# iwing-mrf_shield10.net
KiCad netlist of a schematic drawn in EAGLE
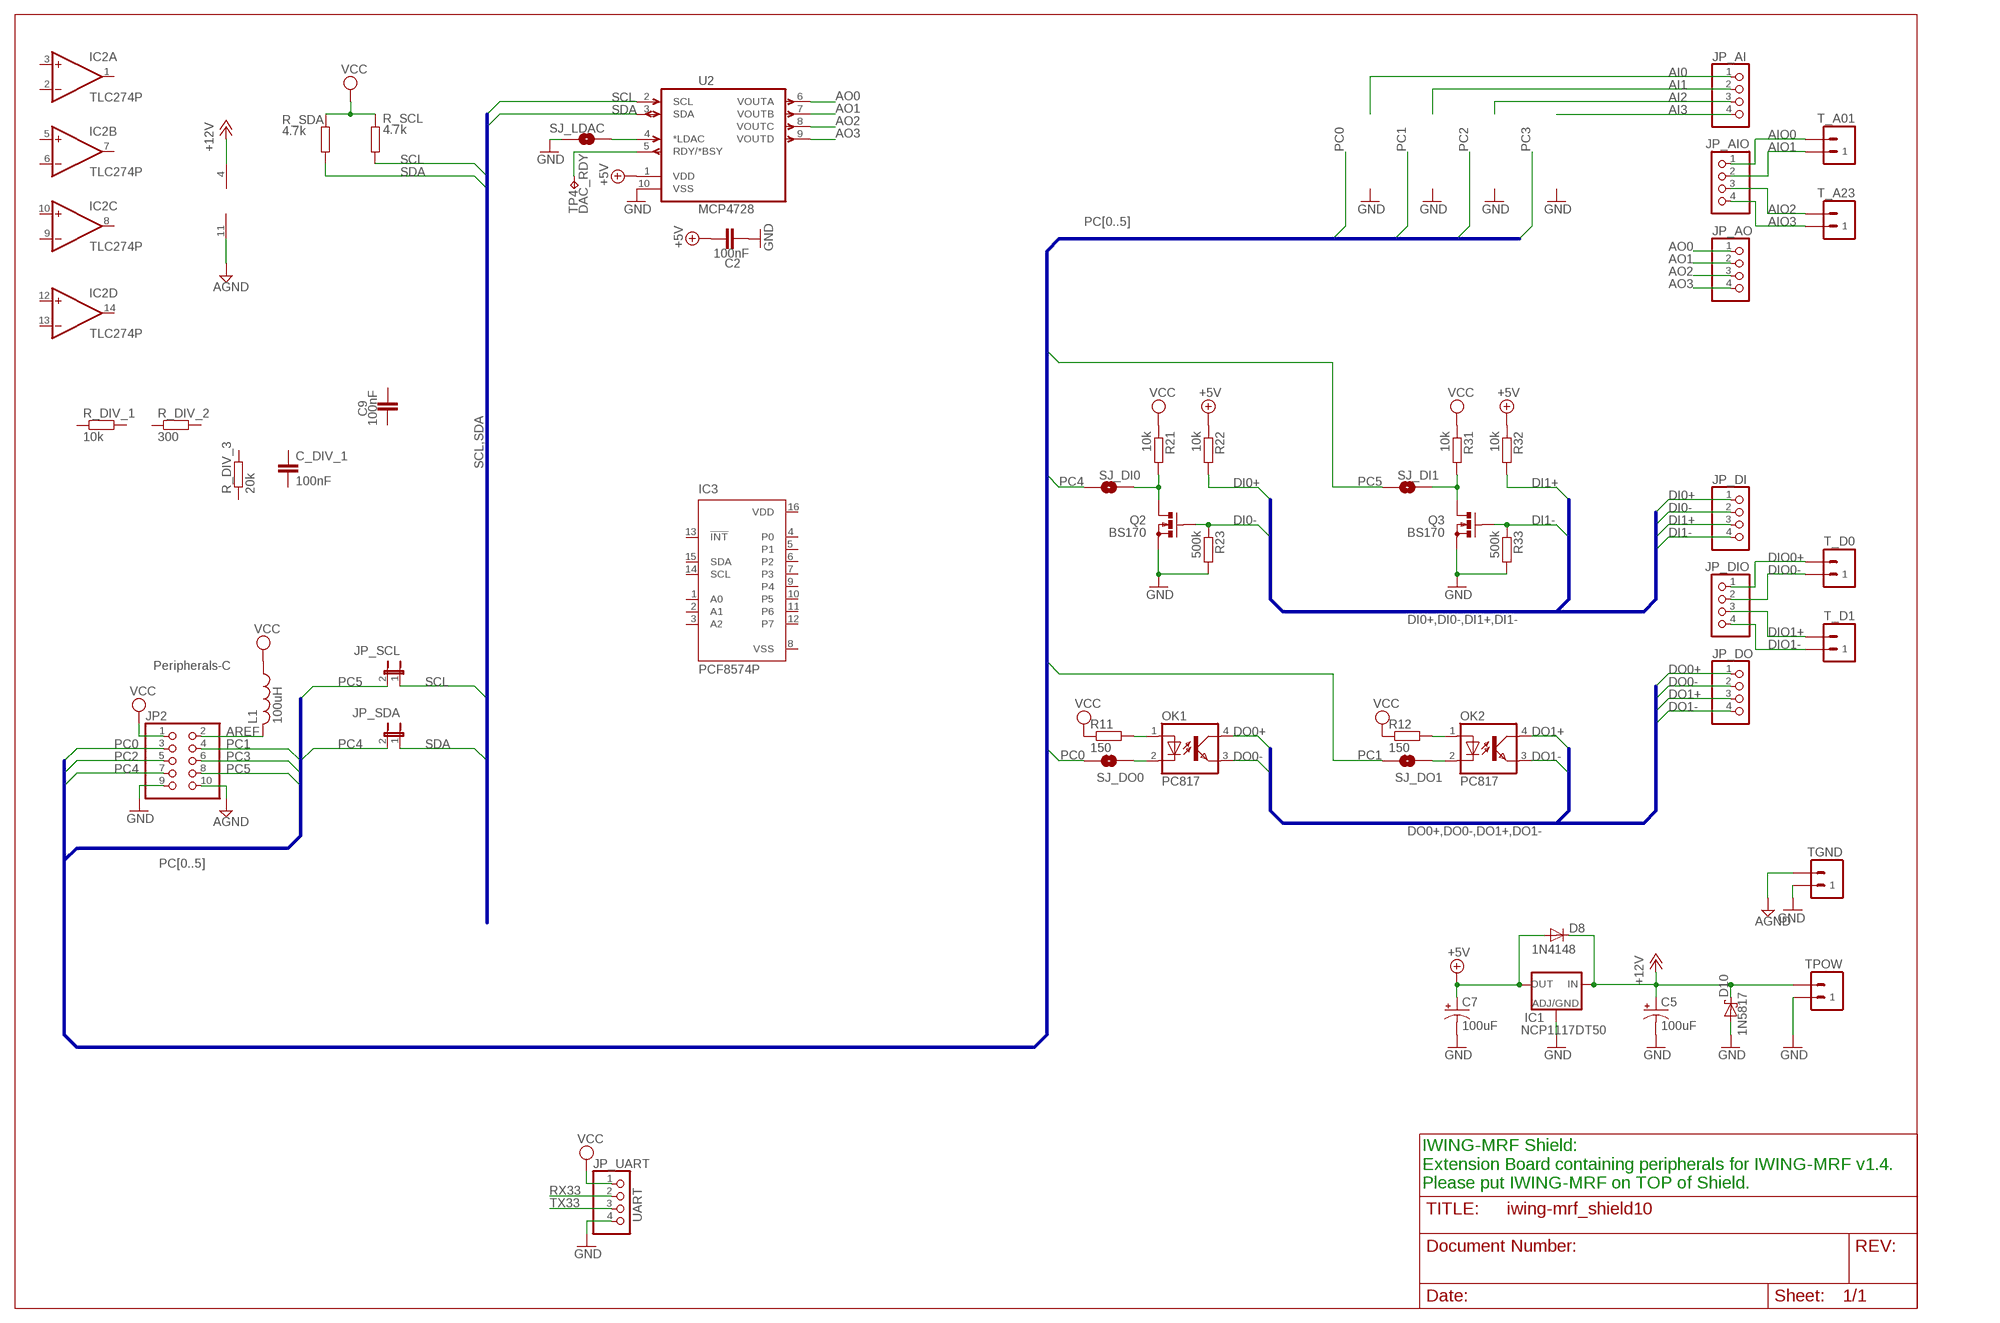
[diagram p0: schematic, sheet 1]

(export (version "E")
  (design (tool "Eeschema 10.0.6"))
  (components
    (comp (ref "C2")
      (value "100nF")
      (footprint "eagle-import:RCL_C050-025X075")
      (libsource (lib "eagle-import") (part "RCL_C-EU050-025X075"))
    )
    (comp (ref "C5")
      (value "100uF")
      (footprint "eagle-import:RCL_E2,5-7")
      (libsource (lib "eagle-import") (part "RCL_CPOL-USE2.5-7"))
    )
    (comp (ref "C7")
      (value "100uF")
      (footprint "eagle-import:RCL_E2,5-7")
      (libsource (lib "eagle-import") (part "RCL_CPOL-USE2.5-7"))
    )
    (comp (ref "C9")
      (value "100nF")
      (footprint "eagle-import:RCL_C050-025X075")
      (libsource (lib "eagle-import") (part "RCL_C-EU050-025X075"))
    )
    (comp (ref "C_DIV_1")
      (value "100nF")
      (footprint "eagle-import:RCL_C050-025X075")
      (libsource (lib "eagle-import") (part "RCL_C-EU050-025X075"))
    )
    (comp (ref "D8")
      (value "1N4148")
      (footprint "eagle-import:DO35-100V")
      (libsource (lib "eagle-import") (part "1N4148-V"))
    )
    (comp (ref "D10")
      (value "1N5817")
      (footprint "eagle-import:DO41-150V")
      (libsource (lib "eagle-import") (part "1N5819-V"))
    )
    (comp (ref "IC1")
      (value "NCP1117DT50")
      (footprint "eagle-import:DPACK")
      (libsource (lib "eagle-import") (part "NCP1117?DT50"))
    )
    (comp (ref "IC2")
      (value "TLC274P")
      (footprint "eagle-import:DIL14")
      (libsource (lib "eagle-import") (part "TLC274P"))
    )
    (comp (ref "IC3")
      (value "PCF8574P")
      (footprint "eagle-import:DIL16")
      (fields (field (name "MPN") "PCF8574PN"))
      (libsource (lib "eagle-import") (part "PCF8574P"))
    )
    (comp (ref "JP2")
      (value "HEADER-2X5")
      (footprint "eagle-import:2X05")
      (libsource (lib "eagle-import") (part "HEADER-2X5"))
    )
    (comp (ref "JP_AI")
      (value "HEADER-1X4ROUND")
      (footprint "eagle-import:1X04_ROUND")
      (libsource (lib "eagle-import") (part "HEADER-1X4ROUND"))
    )
    (comp (ref "JP_AIO")
      (value "HEADER-1X4ROUND")
      (footprint "eagle-import:1X04_ROUND")
      (libsource (lib "eagle-import") (part "HEADER-1X4ROUND"))
    )
    (comp (ref "JP_AO")
      (value "HEADER-1X4ROUND")
      (footprint "eagle-import:1X04_ROUND")
      (libsource (lib "eagle-import") (part "HEADER-1X4ROUND"))
    )
    (comp (ref "JP_DI")
      (value "HEADER-1X4ROUND")
      (footprint "eagle-import:1X04_ROUND")
      (libsource (lib "eagle-import") (part "HEADER-1X4ROUND"))
    )
    (comp (ref "JP_DIO")
      (value "HEADER-1X4ROUND")
      (footprint "eagle-import:1X04_ROUND")
      (libsource (lib "eagle-import") (part "HEADER-1X4ROUND"))
    )
    (comp (ref "JP_DO")
      (value "HEADER-1X4ROUND")
      (footprint "eagle-import:1X04_ROUND")
      (libsource (lib "eagle-import") (part "HEADER-1X4ROUND"))
    )
    (comp (ref "JP_SCL")
      (value "JUMPER-2SMD-NO")
      (footprint "eagle-import:SJ_2S-NO")
      (libsource (lib "eagle-import") (part "JUMPER-2SMD-NO"))
    )
    (comp (ref "JP_SDA")
      (value "JUMPER-2SMD-NO")
      (footprint "eagle-import:SJ_2S-NO")
      (libsource (lib "eagle-import") (part "JUMPER-2SMD-NO"))
    )
    (comp (ref "JP_UART")
      (value "HEADER-1X4ROUND")
      (footprint "eagle-import:1X04_ROUND")
      (libsource (lib "eagle-import") (part "HEADER-1X4ROUND"))
    )
    (comp (ref "L1")
      (value "100uH")
      (footprint "eagle-import:0204_5")
      (libsource (lib "eagle-import") (part "L-US0204/5"))
    )
    (comp (ref "OK1")
      (value "PC817")
      (footprint "eagle-import:DIL04")
      (fields (field (name "MPN") "PC817X4J000F"))
      (libsource (lib "eagle-import") (part "PC817"))
    )
    (comp (ref "OK2")
      (value "PC817")
      (footprint "eagle-import:DIL04")
      (fields (field (name "MPN") "PC817X4J000F"))
      (libsource (lib "eagle-import") (part "PC817"))
    )
    (comp (ref "Q2")
      (value "BS170")
      (footprint "eagle-import:TO92-")
      (libsource (lib "eagle-import") (part "BS170"))
    )
    (comp (ref "Q3")
      (value "BS170")
      (footprint "eagle-import:TO92-")
      (libsource (lib "eagle-import") (part "BS170"))
    )
    (comp (ref "R11")
      (value "150")
      (footprint "eagle-import:0204_5")
      (libsource (lib "eagle-import") (part "R-EU_0204/5"))
    )
    (comp (ref "R12")
      (value "150")
      (footprint "eagle-import:0204_5")
      (libsource (lib "eagle-import") (part "R-EU_0204/5"))
    )
    (comp (ref "R21")
      (value "10k")
      (footprint "eagle-import:0204_5")
      (libsource (lib "eagle-import") (part "R-EU_0204/5"))
    )
    (comp (ref "R22")
      (value "10k")
      (footprint "eagle-import:0204_5")
      (libsource (lib "eagle-import") (part "R-EU_0204/5"))
    )
    (comp (ref "R23")
      (value "500k")
      (footprint "eagle-import:0204_5")
      (libsource (lib "eagle-import") (part "R-EU_0204/5"))
    )
    (comp (ref "R31")
      (value "10k")
      (footprint "eagle-import:0204_5")
      (libsource (lib "eagle-import") (part "R-EU_0204/5"))
    )
    (comp (ref "R32")
      (value "10k")
      (footprint "eagle-import:0204_5")
      (libsource (lib "eagle-import") (part "R-EU_0204/5"))
    )
    (comp (ref "R33")
      (value "500k")
      (footprint "eagle-import:0204_5")
      (libsource (lib "eagle-import") (part "R-EU_0204/5"))
    )
    (comp (ref "R_DIV_1")
      (value "10k")
      (footprint "eagle-import:0204_5")
      (libsource (lib "eagle-import") (part "R-EU_0204/5"))
    )
    (comp (ref "R_DIV_2")
      (value "300")
      (footprint "eagle-import:0204_5")
      (libsource (lib "eagle-import") (part "R-EU_0204/5"))
    )
    (comp (ref "R_DIV_3")
      (value "20k")
      (footprint "eagle-import:0204_5")
      (libsource (lib "eagle-import") (part "R-EU_0204/5"))
    )
    (comp (ref "R_SCL")
      (value "4.7k")
      (footprint "eagle-import:0204_5")
      (libsource (lib "eagle-import") (part "R-EU_0204/5"))
    )
    (comp (ref "R_SDA")
      (value "4.7k")
      (footprint "eagle-import:0204_5")
      (libsource (lib "eagle-import") (part "R-EU_0204/5"))
    )
    (comp (ref "SJ_DI0")
      (value "SOLDERJUMPERNO")
      (footprint "eagle-import:SJ_2S-NO")
      (libsource (lib "eagle-import") (part "SOLDERJUMPERNO"))
    )
    (comp (ref "SJ_DI1")
      (value "SOLDERJUMPERNO")
      (footprint "eagle-import:SJ_2S-NO")
      (libsource (lib "eagle-import") (part "SOLDERJUMPERNO"))
    )
    (comp (ref "SJ_DO0")
      (value "SOLDERJUMPERNO")
      (footprint "eagle-import:SJ_2S-NO")
      (libsource (lib "eagle-import") (part "SOLDERJUMPERNO"))
    )
    (comp (ref "SJ_DO1")
      (value "SOLDERJUMPERNO")
      (footprint "eagle-import:SJ_2S-NO")
      (libsource (lib "eagle-import") (part "SOLDERJUMPERNO"))
    )
    (comp (ref "SJ_LDAC")
      (value "SOLDERJUMPERNO")
      (footprint "eagle-import:SJ_2S-NO")
      (libsource (lib "eagle-import") (part "SOLDERJUMPERNO"))
    )
    (comp (ref "TGND")
      (value "ST02-5MM")
      (footprint "eagle-import:EK500V-02P")
      (libsource (lib "eagle-import") (part "ST02-5MM"))
    )
    (comp (ref "TP4")
      (value "TPPAD1-13")
      (footprint "eagle-import:P1-13")
      (fields (field (name "TP_SIGNAL_NAME") "DAC_RDY"))
      (libsource (lib "eagle-import") (part "TPPAD1-13"))
    )
    (comp (ref "TPOW")
      (value "ST02-5MM")
      (footprint "eagle-import:EK500V-02P")
      (libsource (lib "eagle-import") (part "ST02-5MM"))
    )
    (comp (ref "T_A01")
      (value "ST02-5MM")
      (footprint "eagle-import:EK500V-02P")
      (libsource (lib "eagle-import") (part "ST02-5MM"))
    )
    (comp (ref "T_A23")
      (value "ST02-5MM")
      (footprint "eagle-import:EK500V-02P")
      (libsource (lib "eagle-import") (part "ST02-5MM"))
    )
    (comp (ref "T_D0")
      (value "ST02-5MM")
      (footprint "eagle-import:EK500V-02P")
      (libsource (lib "eagle-import") (part "ST02-5MM"))
    )
    (comp (ref "T_D1")
      (value "ST02-5MM")
      (footprint "eagle-import:EK500V-02P")
      (libsource (lib "eagle-import") (part "ST02-5MM"))
    )
    (comp (ref "U2")
      (value "MCP4728")
      (footprint "eagle-import:MSOP-10")
      (libsource (lib "eagle-import") (part "MCP4728-E/UN"))
    )
  )
  (nets
    (net (code "1") (name "+5V") (class "Default")
      (node (ref "C2") (pin "1") (pinfunction "1_1") (pintype "passive"))
      (node (ref "C7") (pin "+") (pinfunction "+_+") (pintype "passive"))
      (node (ref "D8") (pin "A") (pinfunction "A_A") (pintype "passive"))
      (node (ref "IC1") (pin "4") (pinfunction "OUT_4") (pintype "passive"))
      (node (ref "R22") (pin "1") (pinfunction "1_1") (pintype "passive"))
      (node (ref "R32") (pin "1") (pinfunction "1_1") (pintype "passive"))
      (node (ref "U2") (pin "1") (pinfunction "VDD_1") (pintype "power_in"))
    )
    (net (code "2") (name "+12V") (class "Default")
      (node (ref "C5") (pin "+") (pinfunction "+_+") (pintype "passive"))
      (node (ref "D10") (pin "C") (pinfunction "C_C") (pintype "passive"))
      (node (ref "D8") (pin "C") (pinfunction "C_C") (pintype "passive"))
      (node (ref "IC1") (pin "3") (pinfunction "IN_3") (pintype "input"))
      (node (ref "IC2") (pin "4") (pinfunction "V+_4") (pintype "power_in"))
      (node (ref "TPOW") (pin "P$2") (pinfunction "2_P$2") (pintype "passive"))
    )
    (net (code "3") (name "/AI0") (class "Default")
      (node (ref "JP_AI") (pin "1") (pinfunction "1_1") (pintype "passive"))
    )
    (net (code "4") (name "/AI1") (class "Default")
      (node (ref "JP_AI") (pin "2") (pinfunction "2_2") (pintype "passive"))
    )
    (net (code "5") (name "/AI2") (class "Default")
      (node (ref "JP_AI") (pin "3") (pinfunction "3_3") (pintype "passive"))
    )
    (net (code "6") (name "/AI3") (class "Default")
      (node (ref "JP_AI") (pin "4") (pinfunction "4_4") (pintype "passive"))
    )
    (net (code "7") (name "/AIO0") (class "Default")
      (node (ref "JP_AIO") (pin "1") (pinfunction "1_1") (pintype "passive"))
      (node (ref "T_A01") (pin "P$2") (pinfunction "2_P$2") (pintype "passive"))
    )
    (net (code "8") (name "/AIO1") (class "Default")
      (node (ref "JP_AIO") (pin "2") (pinfunction "2_2") (pintype "passive"))
      (node (ref "T_A01") (pin "P$1") (pinfunction "1_P$1") (pintype "passive"))
    )
    (net (code "9") (name "/AIO2") (class "Default")
      (node (ref "JP_AIO") (pin "3") (pinfunction "3_3") (pintype "passive"))
      (node (ref "T_A23") (pin "P$2") (pinfunction "2_P$2") (pintype "passive"))
    )
    (net (code "10") (name "/AIO3") (class "Default")
      (node (ref "JP_AIO") (pin "4") (pinfunction "4_4") (pintype "passive"))
      (node (ref "T_A23") (pin "P$1") (pinfunction "1_P$1") (pintype "passive"))
    )
    (net (code "11") (name "/AO0") (class "Default")
      (node (ref "JP_AO") (pin "1") (pinfunction "1_1") (pintype "passive"))
      (node (ref "U2") (pin "6") (pinfunction "VOUTA_6") (pintype "output"))
    )
    (net (code "12") (name "/AO1") (class "Default")
      (node (ref "JP_AO") (pin "2") (pinfunction "2_2") (pintype "passive"))
      (node (ref "U2") (pin "7") (pinfunction "VOUTB_7") (pintype "output"))
    )
    (net (code "13") (name "/AO2") (class "Default")
      (node (ref "JP_AO") (pin "3") (pinfunction "3_3") (pintype "passive"))
      (node (ref "U2") (pin "8") (pinfunction "VOUTC_8") (pintype "output"))
    )
    (net (code "14") (name "/AO3") (class "Default")
      (node (ref "JP_AO") (pin "4") (pinfunction "4_4") (pintype "passive"))
      (node (ref "U2") (pin "9") (pinfunction "VOUTD_9") (pintype "output"))
    )
    (net (code "15") (name "/AREF") (class "Default")
      (node (ref "JP2") (pin "2") (pinfunction "2_2") (pintype "passive"))
      (node (ref "L1") (pin "2") (pinfunction "2_2") (pintype "passive"))
    )
    (net (code "16") (name "/DI0+") (class "Default")
      (node (ref "JP_DI") (pin "1") (pinfunction "1_1") (pintype "passive"))
      (node (ref "R22") (pin "2") (pinfunction "2_2") (pintype "passive"))
    )
    (net (code "17") (name "/DI0-") (class "Default")
      (node (ref "JP_DI") (pin "2") (pinfunction "2_2") (pintype "passive"))
      (node (ref "Q2") (pin "2") (pinfunction "G_2") (pintype "passive"))
      (node (ref "R23") (pin "1") (pinfunction "1_1") (pintype "passive"))
    )
    (net (code "18") (name "/DI1+") (class "Default")
      (node (ref "JP_DI") (pin "3") (pinfunction "3_3") (pintype "passive"))
      (node (ref "R32") (pin "2") (pinfunction "2_2") (pintype "passive"))
    )
    (net (code "19") (name "/DI1-") (class "Default")
      (node (ref "JP_DI") (pin "4") (pinfunction "4_4") (pintype "passive"))
      (node (ref "Q3") (pin "2") (pinfunction "G_2") (pintype "passive"))
      (node (ref "R33") (pin "1") (pinfunction "1_1") (pintype "passive"))
    )
    (net (code "20") (name "/DIO0+") (class "Default")
      (node (ref "JP_DIO") (pin "1") (pinfunction "1_1") (pintype "passive"))
      (node (ref "T_D0") (pin "P$2") (pinfunction "2_P$2") (pintype "passive"))
    )
    (net (code "21") (name "/DIO0-") (class "Default")
      (node (ref "JP_DIO") (pin "2") (pinfunction "2_2") (pintype "passive"))
      (node (ref "T_D0") (pin "P$1") (pinfunction "1_P$1") (pintype "passive"))
    )
    (net (code "22") (name "/DIO1+") (class "Default")
      (node (ref "JP_DIO") (pin "3") (pinfunction "3_3") (pintype "passive"))
      (node (ref "T_D1") (pin "P$2") (pinfunction "2_P$2") (pintype "passive"))
    )
    (net (code "23") (name "/DIO1-") (class "Default")
      (node (ref "JP_DIO") (pin "4") (pinfunction "4_4") (pintype "passive"))
      (node (ref "T_D1") (pin "P$1") (pinfunction "1_P$1") (pintype "passive"))
    )
    (net (code "24") (name "/DO0+") (class "Default")
      (node (ref "JP_DO") (pin "1") (pinfunction "1_1") (pintype "passive"))
      (node (ref "OK1") (pin "4") (pinfunction "COL_4") (pintype "passive"))
    )
    (net (code "25") (name "/DO0-") (class "Default")
      (node (ref "JP_DO") (pin "2") (pinfunction "2_2") (pintype "passive"))
      (node (ref "OK1") (pin "3") (pinfunction "EMIT_3") (pintype "passive"))
    )
    (net (code "26") (name "/DO1+") (class "Default")
      (node (ref "JP_DO") (pin "3") (pinfunction "3_3") (pintype "passive"))
      (node (ref "OK2") (pin "4") (pinfunction "COL_4") (pintype "passive"))
    )
    (net (code "27") (name "/DO1-") (class "Default")
      (node (ref "JP_DO") (pin "4") (pinfunction "4_4") (pintype "passive"))
      (node (ref "OK2") (pin "3") (pinfunction "EMIT_3") (pintype "passive"))
    )
    (net (code "28") (name "/PC0") (class "Default")
      (node (ref "JP2") (pin "3") (pinfunction "3_3") (pintype "passive"))
      (node (ref "SJ_DO0") (pin "1") (pinfunction "1_1") (pintype "passive"))
    )
    (net (code "29") (name "/PC1") (class "Default")
      (node (ref "JP2") (pin "4") (pinfunction "4_4") (pintype "passive"))
      (node (ref "SJ_DO1") (pin "1") (pinfunction "1_1") (pintype "passive"))
    )
    (net (code "30") (name "/PC2") (class "Default")
      (node (ref "JP2") (pin "5") (pinfunction "5_5") (pintype "passive"))
    )
    (net (code "31") (name "/PC3") (class "Default")
      (node (ref "JP2") (pin "6") (pinfunction "6_6") (pintype "passive"))
    )
    (net (code "32") (name "/PC4") (class "Default")
      (node (ref "JP2") (pin "7") (pinfunction "7_7") (pintype "passive"))
      (node (ref "JP_SDA") (pin "2") (pinfunction "2_2") (pintype "passive"))
      (node (ref "SJ_DI0") (pin "2") (pinfunction "2_2") (pintype "passive"))
    )
    (net (code "33") (name "/PC5") (class "Default")
      (node (ref "JP2") (pin "8") (pinfunction "8_8") (pintype "passive"))
      (node (ref "JP_SCL") (pin "2") (pinfunction "2_2") (pintype "passive"))
      (node (ref "SJ_DI1") (pin "2") (pinfunction "2_2") (pintype "passive"))
    )
    (net (code "35") (name "/RX33") (class "Default")
      (node (ref "JP_UART") (pin "2") (pinfunction "2_2") (pintype "passive"))
    )
    (net (code "36") (name "/SCL") (class "Default")
      (node (ref "JP_SCL") (pin "1") (pinfunction "1_1") (pintype "passive"))
      (node (ref "R_SCL") (pin "2") (pinfunction "2_2") (pintype "passive"))
      (node (ref "U2") (pin "2") (pinfunction "SCL_2") (pintype "input"))
    )
    (net (code "37") (name "/SDA") (class "Default")
      (node (ref "JP_SDA") (pin "1") (pinfunction "1_1") (pintype "passive"))
      (node (ref "R_SDA") (pin "2") (pinfunction "2_2") (pintype "passive"))
      (node (ref "U2") (pin "3") (pinfunction "SDA_3") (pintype "bidirectional"))
    )
    (net (code "38") (name "/TX33") (class "Default")
      (node (ref "JP_UART") (pin "3") (pinfunction "3_3") (pintype "passive"))
    )
    (net (code "39") (name "/VDD") (class "Default")
      (node (ref "IC3") (pin "16") (pinfunction "VDD_16") (pintype "power_in"))
    )
    (net (code "40") (name "/VSS") (class "Default")
      (node (ref "IC3") (pin "8") (pinfunction "VSS_8") (pintype "power_in"))
    )
    (net (code "44") (name "AGND") (class "Default")
      (node (ref "IC2") (pin "11") (pinfunction "V-_11") (pintype "power_in"))
      (node (ref "JP2") (pin "10") (pinfunction "10_10") (pintype "passive"))
      (node (ref "TGND") (pin "P$2") (pinfunction "2_P$2") (pintype "passive"))
    )
    (net (code "45") (name "GND") (class "Default")
      (node (ref "C2") (pin "2") (pinfunction "2_2") (pintype "passive"))
      (node (ref "C5") (pin "-") (pinfunction "-_-") (pintype "passive"))
      (node (ref "C7") (pin "-") (pinfunction "-_-") (pintype "passive"))
      (node (ref "D10") (pin "A") (pinfunction "A_A") (pintype "passive"))
      (node (ref "IC1") (pin "1") (pinfunction "ADJ_1") (pintype "input"))
      (node (ref "JP2") (pin "9") (pinfunction "9_9") (pintype "passive"))
      (node (ref "JP_UART") (pin "4") (pinfunction "4_4") (pintype "passive"))
      (node (ref "Q2") (pin "3") (pinfunction "S_3") (pintype "passive"))
      (node (ref "Q3") (pin "3") (pinfunction "S_3") (pintype "passive"))
      (node (ref "R23") (pin "2") (pinfunction "2_2") (pintype "passive"))
      (node (ref "R33") (pin "2") (pinfunction "2_2") (pintype "passive"))
      (node (ref "SJ_LDAC") (pin "1") (pinfunction "1_1") (pintype "passive"))
      (node (ref "TGND") (pin "P$1") (pinfunction "1_P$1") (pintype "passive"))
      (node (ref "TPOW") (pin "P$1") (pinfunction "1_P$1") (pintype "passive"))
      (node (ref "U2") (pin "10") (pinfunction "VSS_10") (pintype "power_in"))
    )
    (net (code "46") (name "Net-(OK1-A)") (class "Default")
      (node (ref "OK1") (pin "1") (pinfunction "A_1") (pintype "passive"))
      (node (ref "R11") (pin "2") (pinfunction "2_2") (pintype "passive"))
    )
    (net (code "47") (name "Net-(OK1-C)") (class "Default")
      (node (ref "OK1") (pin "2") (pinfunction "C_2") (pintype "passive"))
      (node (ref "SJ_DO0") (pin "2") (pinfunction "2_2") (pintype "passive"))
    )
    (net (code "48") (name "Net-(OK2-A)") (class "Default")
      (node (ref "OK2") (pin "1") (pinfunction "A_1") (pintype "passive"))
      (node (ref "R12") (pin "2") (pinfunction "2_2") (pintype "passive"))
    )
    (net (code "49") (name "Net-(OK2-C)") (class "Default")
      (node (ref "OK2") (pin "2") (pinfunction "C_2") (pintype "passive"))
      (node (ref "SJ_DO1") (pin "2") (pinfunction "2_2") (pintype "passive"))
    )
    (net (code "50") (name "Net-(Q2-D)") (class "Default")
      (node (ref "Q2") (pin "1") (pinfunction "D_1") (pintype "passive"))
      (node (ref "R21") (pin "2") (pinfunction "2_2") (pintype "passive"))
      (node (ref "SJ_DI0") (pin "1") (pinfunction "1_1") (pintype "passive"))
    )
    (net (code "51") (name "Net-(Q3-D)") (class "Default")
      (node (ref "Q3") (pin "1") (pinfunction "D_1") (pintype "passive"))
      (node (ref "R31") (pin "2") (pinfunction "2_2") (pintype "passive"))
      (node (ref "SJ_DI1") (pin "1") (pinfunction "1_1") (pintype "passive"))
    )
    (net (code "52") (name "Net-(U2-*LDAC)") (class "Default")
      (node (ref "SJ_LDAC") (pin "2") (pinfunction "2_2") (pintype "passive"))
      (node (ref "U2") (pin "4") (pinfunction "*LDAC_4") (pintype "input"))
    )
    (net (code "53") (name "Net-(U2-RDY{slash}*BSY)") (class "Default")
      (node (ref "TP4") (pin "TP") (pinfunction "TP_TP") (pintype "input"))
      (node (ref "U2") (pin "5") (pinfunction "RDY/*BSY_5") (pintype "output"))
    )
    (net (code "54") (name "VCC") (class "Default")
      (node (ref "JP2") (pin "1") (pinfunction "1_1") (pintype "passive"))
      (node (ref "JP_UART") (pin "1") (pinfunction "1_1") (pintype "passive"))
      (node (ref "L1") (pin "1") (pinfunction "1_1") (pintype "passive"))
      (node (ref "R11") (pin "1") (pinfunction "1_1") (pintype "passive"))
      (node (ref "R12") (pin "1") (pinfunction "1_1") (pintype "passive"))
      (node (ref "R21") (pin "1") (pinfunction "1_1") (pintype "passive"))
      (node (ref "R31") (pin "1") (pinfunction "1_1") (pintype "passive"))
      (node (ref "R_SCL") (pin "1") (pinfunction "1_1") (pintype "passive"))
      (node (ref "R_SDA") (pin "1") (pinfunction "1_1") (pintype "passive"))
    )
    (net (code "55") (name "unconnected-(C9-Pad1)") (class "Default")
      (node (ref "C9") (pin "1") (pinfunction "1_1") (pintype "passive"))
    )
    (net (code "56") (name "unconnected-(C9-Pad2)") (class "Default")
      (node (ref "C9") (pin "2") (pinfunction "2_2") (pintype "passive"))
    )
    (net (code "57") (name "unconnected-(C_DIV_1-Pad1)") (class "Default")
      (node (ref "C_DIV_1") (pin "1") (pinfunction "1_1") (pintype "passive"))
    )
    (net (code "58") (name "unconnected-(C_DIV_1-Pad2)") (class "Default")
      (node (ref "C_DIV_1") (pin "2") (pinfunction "2_2") (pintype "passive"))
    )
    (net (code "59") (name "unconnected-(IC2A-+IN-Pad3)") (class "Default")
      (node (ref "IC2") (pin "3") (pinfunction "+IN_3") (pintype "input"))
    )
    (net (code "60") (name "unconnected-(IC2A--IN-Pad2)") (class "Default")
      (node (ref "IC2") (pin "2") (pinfunction "-IN_2") (pintype "input"))
    )
    (net (code "61") (name "unconnected-(IC2A-OUT-Pad1)") (class "Default")
      (node (ref "IC2") (pin "1") (pinfunction "OUT_1") (pintype "output"))
    )
    (net (code "62") (name "unconnected-(IC2B-+IN-Pad5)") (class "Default")
      (node (ref "IC2") (pin "5") (pinfunction "+IN_5") (pintype "input"))
    )
    (net (code "63") (name "unconnected-(IC2B--IN-Pad6)") (class "Default")
      (node (ref "IC2") (pin "6") (pinfunction "-IN_6") (pintype "input"))
    )
    (net (code "64") (name "unconnected-(IC2B-OUT-Pad7)") (class "Default")
      (node (ref "IC2") (pin "7") (pinfunction "OUT_7") (pintype "output"))
    )
    (net (code "65") (name "unconnected-(IC2C-+IN-Pad10)") (class "Default")
      (node (ref "IC2") (pin "10") (pinfunction "+IN_10") (pintype "input"))
    )
    (net (code "66") (name "unconnected-(IC2C--IN-Pad9)") (class "Default")
      (node (ref "IC2") (pin "9") (pinfunction "-IN_9") (pintype "input"))
    )
    (net (code "67") (name "unconnected-(IC2C-OUT-Pad8)") (class "Default")
      (node (ref "IC2") (pin "8") (pinfunction "OUT_8") (pintype "output"))
    )
    (net (code "68") (name "unconnected-(IC2D-+IN-Pad12)") (class "Default")
      (node (ref "IC2") (pin "12") (pinfunction "+IN_12") (pintype "input"))
    )
    (net (code "69") (name "unconnected-(IC2D--IN-Pad13)") (class "Default")
      (node (ref "IC2") (pin "13") (pinfunction "-IN_13") (pintype "input"))
    )
    (net (code "70") (name "unconnected-(IC2D-OUT-Pad14)") (class "Default")
      (node (ref "IC2") (pin "14") (pinfunction "OUT_14") (pintype "output"))
    )
    (net (code "71") (name "unconnected-(IC3-A0-Pad1)") (class "Default")
      (node (ref "IC3") (pin "1") (pinfunction "A0_1") (pintype "input"))
    )
    (net (code "72") (name "unconnected-(IC3-A1-Pad2)") (class "Default")
      (node (ref "IC3") (pin "2") (pinfunction "A1_2") (pintype "input"))
    )
    (net (code "73") (name "unconnected-(IC3-A2-Pad3)") (class "Default")
      (node (ref "IC3") (pin "3") (pinfunction "A2_3") (pintype "input"))
    )
    (net (code "74") (name "unconnected-(IC3-P0-Pad4)") (class "Default")
      (node (ref "IC3") (pin "4") (pinfunction "P0_4") (pintype "bidirectional"))
    )
    (net (code "75") (name "unconnected-(IC3-P1-Pad5)") (class "Default")
      (node (ref "IC3") (pin "5") (pinfunction "P1_5") (pintype "bidirectional"))
    )
    (net (code "76") (name "unconnected-(IC3-P2-Pad6)") (class "Default")
      (node (ref "IC3") (pin "6") (pinfunction "P2_6") (pintype "bidirectional"))
    )
    (net (code "77") (name "unconnected-(IC3-P3-Pad7)") (class "Default")
      (node (ref "IC3") (pin "7") (pinfunction "P3_7") (pintype "bidirectional"))
    )
    (net (code "78") (name "unconnected-(IC3-P4-Pad9)") (class "Default")
      (node (ref "IC3") (pin "9") (pinfunction "P4_9") (pintype "bidirectional"))
    )
    (net (code "79") (name "unconnected-(IC3-P5-Pad10)") (class "Default")
      (node (ref "IC3") (pin "10") (pinfunction "P5_10") (pintype "bidirectional"))
    )
    (net (code "80") (name "unconnected-(IC3-P6-Pad11)") (class "Default")
      (node (ref "IC3") (pin "11") (pinfunction "P6_11") (pintype "bidirectional"))
    )
    (net (code "81") (name "unconnected-(IC3-P7-Pad12)") (class "Default")
      (node (ref "IC3") (pin "12") (pinfunction "P7_12") (pintype "bidirectional"))
    )
    (net (code "82") (name "unconnected-(IC3-SCL-Pad14)") (class "Default")
      (node (ref "IC3") (pin "14") (pinfunction "SCL_14") (pintype "input"))
    )
    (net (code "83") (name "unconnected-(IC3-SDA-Pad15)") (class "Default")
      (node (ref "IC3") (pin "15") (pinfunction "SDA_15") (pintype "bidirectional"))
    )
    (net (code "84") (name "unconnected-(IC3-~{INT}-Pad13)") (class "Default")
      (node (ref "IC3") (pin "13") (pinfunction "~{INT}_13") (pintype "output"))
    )
    (net (code "85") (name "unconnected-(R_DIV_1-Pad1)") (class "Default")
      (node (ref "R_DIV_1") (pin "1") (pinfunction "1_1") (pintype "passive"))
    )
    (net (code "86") (name "unconnected-(R_DIV_1-Pad2)") (class "Default")
      (node (ref "R_DIV_1") (pin "2") (pinfunction "2_2") (pintype "passive"))
    )
    (net (code "87") (name "unconnected-(R_DIV_2-Pad1)") (class "Default")
      (node (ref "R_DIV_2") (pin "1") (pinfunction "1_1") (pintype "passive"))
    )
    (net (code "88") (name "unconnected-(R_DIV_2-Pad2)") (class "Default")
      (node (ref "R_DIV_2") (pin "2") (pinfunction "2_2") (pintype "passive"))
    )
    (net (code "89") (name "unconnected-(R_DIV_3-Pad1)") (class "Default")
      (node (ref "R_DIV_3") (pin "1") (pinfunction "1_1") (pintype "passive"))
    )
    (net (code "90") (name "unconnected-(R_DIV_3-Pad2)") (class "Default")
      (node (ref "R_DIV_3") (pin "2") (pinfunction "2_2") (pintype "passive"))
    )
  )
)
